# Module.net
KiCad netlist of a schematic drawn in EAGLE
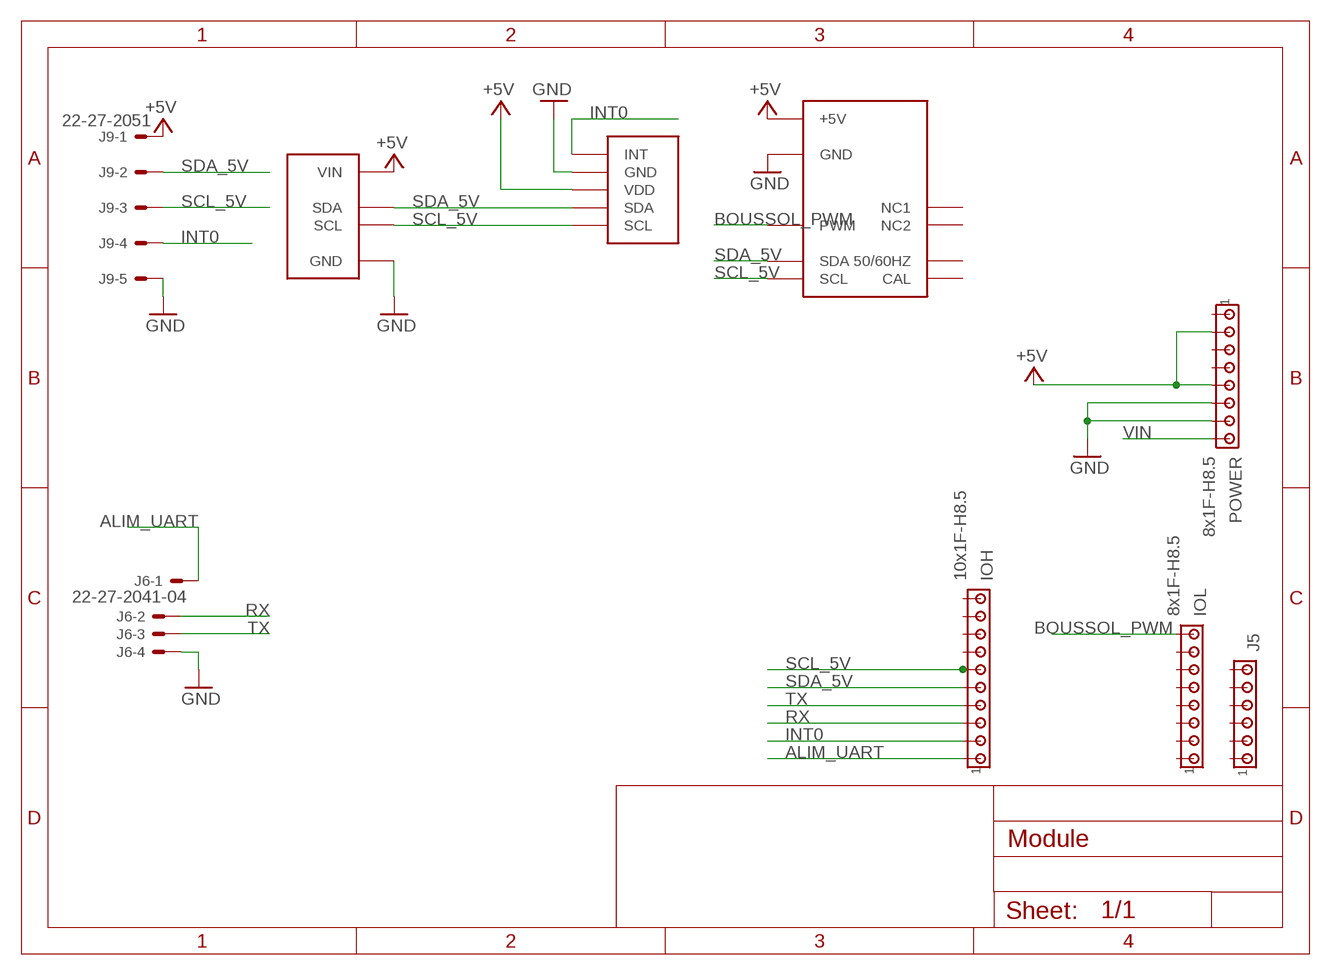
[diagram p0: schematic, sheet 1]

(export (version "E")
  (design (tool "Eeschema 10.0.6"))
  (components
    (comp (ref "IOH")
      (value "10x1F-H8.5")
      (footprint "eagle-import:10X10MTA")
      (libsource (lib "eagle-import") (part "MTA10-100"))
    )
    (comp (ref "IOL")
      (value "8x1F-H8.5")
      (footprint "eagle-import:10X08MTA")
      (libsource (lib "eagle-import") (part "MTA08-100"))
    )
    (comp (ref "J5")
      (value "MTA06-100")
      (footprint "eagle-import:10X06MTA")
      (libsource (lib "eagle-import") (part "MTA06-100"))
    )
    (comp (ref "J6")
      (value "22-27-2041-04")
      (footprint "eagle-import:6410-04")
      (libsource (lib "eagle-import") (part "22-?-0427-2041"))
    )
    (comp (ref "J9")
      (value "22-27-2051")
      (footprint "eagle-import:6410-05")
      (libsource (lib "eagle-import") (part "22-?-0527-2051"))
    )
    (comp (ref "POWER")
      (value "8x1F-H8.5")
      (footprint "eagle-import:10X08MTA")
      (libsource (lib "eagle-import") (part "MTA08-100"))
    )
    (comp (ref "U$1")
      (value "SRF10")
      (footprint "eagle-import:SRF10")
      (libsource (lib "eagle-import") (part "SRF10"))
    )
    (comp (ref "U$2")
      (value "MPU9150")
      (footprint "eagle-import:MPU9150")
      (libsource (lib "eagle-import") (part "MPU9150"))
    )
    (comp (ref "U$6")
      (value "CMPS03")
      (footprint "eagle-import:CMPS03")
      (libsource (lib "eagle-import") (part "CMPS03"))
    )
  )
  (nets
    (net (code "1") (name "+5V") (class "Default")
      (node (ref "J9") (pin "1") (pinfunction "S_1") (pintype "passive"))
      (node (ref "POWER") (pin "2") (pinfunction "2_2") (pintype "passive"))
      (node (ref "POWER") (pin "5") (pinfunction "5_5") (pintype "passive"))
      (node (ref "U$1") (pin "P$4") (pinfunction "VIN_P$4") (pintype "power_in"))
      (node (ref "U$2") (pin "P$3") (pinfunction "VDD_P$3") (pintype "power_in"))
      (node (ref "U$6") (pin "P$1") (pinfunction "+5V_P$1") (pintype "power_in"))
    )
    (net (code "2") (name "/ALIM_UART") (class "Default")
      (node (ref "IOH") (pin "1") (pinfunction "1_1") (pintype "passive"))
      (node (ref "J6") (pin "1") (pinfunction "S_1") (pintype "passive"))
    )
    (net (code "3") (name "/BOUSSOL_PWM") (class "Default")
      (node (ref "IOL") (pin "8") (pinfunction "8_8") (pintype "passive"))
      (node (ref "U$6") (pin "P$4") (pinfunction "PWM_P$4") (pintype "output"))
    )
    (net (code "4") (name "/INT0") (class "Default")
      (node (ref "IOH") (pin "2") (pinfunction "2_2") (pintype "passive"))
      (node (ref "J9") (pin "4") (pinfunction "S_4") (pintype "passive"))
      (node (ref "U$2") (pin "P$1") (pinfunction "INT_P$1") (pintype "output"))
    )
    (net (code "5") (name "/RX") (class "Default")
      (node (ref "IOH") (pin "3") (pinfunction "3_3") (pintype "passive"))
      (node (ref "J6") (pin "2") (pinfunction "S_2") (pintype "passive"))
    )
    (net (code "6") (name "/SCL_5V") (class "Default")
      (node (ref "IOH") (pin "6") (pinfunction "6_6") (pintype "passive"))
      (node (ref "J9") (pin "3") (pinfunction "S_3") (pintype "passive"))
      (node (ref "U$1") (pin "P$2") (pinfunction "SCL_P$2") (pintype "bidirectional"))
      (node (ref "U$2") (pin "P$5") (pinfunction "SCL_P$5") (pintype "bidirectional"))
      (node (ref "U$6") (pin "P$2") (pinfunction "SCL_P$2") (pintype "bidirectional"))
    )
    (net (code "7") (name "/SDA_5V") (class "Default")
      (node (ref "IOH") (pin "5") (pinfunction "5_5") (pintype "passive"))
      (node (ref "J9") (pin "2") (pinfunction "S_2") (pintype "passive"))
      (node (ref "U$1") (pin "P$3") (pinfunction "SDA_P$3") (pintype "bidirectional"))
      (node (ref "U$2") (pin "P$4") (pinfunction "SDA_P$4") (pintype "bidirectional"))
      (node (ref "U$6") (pin "P$3") (pinfunction "SDA_P$3") (pintype "bidirectional"))
    )
    (net (code "8") (name "/TX") (class "Default")
      (node (ref "IOH") (pin "4") (pinfunction "4_4") (pintype "passive"))
      (node (ref "J6") (pin "3") (pinfunction "S_3") (pintype "passive"))
    )
    (net (code "9") (name "/VIN") (class "Default")
      (node (ref "POWER") (pin "8") (pinfunction "8_8") (pintype "passive"))
    )
    (net (code "10") (name "GND") (class "Default")
      (node (ref "J6") (pin "4") (pinfunction "S_4") (pintype "passive"))
      (node (ref "J9") (pin "5") (pinfunction "S_5") (pintype "passive"))
      (node (ref "POWER") (pin "6") (pinfunction "6_6") (pintype "passive"))
      (node (ref "POWER") (pin "7") (pinfunction "7_7") (pintype "passive"))
      (node (ref "U$1") (pin "P$1") (pinfunction "GND_P$1") (pintype "power_in"))
      (node (ref "U$2") (pin "P$2") (pinfunction "GND_P$2") (pintype "power_in"))
      (node (ref "U$6") (pin "P$9") (pinfunction "GND_P$9") (pintype "power_in"))
    )
    (net (code "11") (name "unconnected-(IOH-Pad7)") (class "Default")
      (node (ref "IOH") (pin "7") (pinfunction "7_7") (pintype "passive"))
    )
    (net (code "12") (name "unconnected-(IOH-Pad8)") (class "Default")
      (node (ref "IOH") (pin "8") (pinfunction "8_8") (pintype "passive"))
    )
    (net (code "13") (name "unconnected-(IOH-Pad9)") (class "Default")
      (node (ref "IOH") (pin "9") (pinfunction "9_9") (pintype "passive"))
    )
    (net (code "14") (name "unconnected-(IOH-Pad10)") (class "Default")
      (node (ref "IOH") (pin "10") (pinfunction "10_10") (pintype "passive"))
    )
    (net (code "15") (name "unconnected-(IOL-Pad1)") (class "Default")
      (node (ref "IOL") (pin "1") (pinfunction "1_1") (pintype "passive"))
    )
    (net (code "16") (name "unconnected-(IOL-Pad2)") (class "Default")
      (node (ref "IOL") (pin "2") (pinfunction "2_2") (pintype "passive"))
    )
    (net (code "17") (name "unconnected-(IOL-Pad3)") (class "Default")
      (node (ref "IOL") (pin "3") (pinfunction "3_3") (pintype "passive"))
    )
    (net (code "18") (name "unconnected-(IOL-Pad4)") (class "Default")
      (node (ref "IOL") (pin "4") (pinfunction "4_4") (pintype "passive"))
    )
    (net (code "19") (name "unconnected-(IOL-Pad5)") (class "Default")
      (node (ref "IOL") (pin "5") (pinfunction "5_5") (pintype "passive"))
    )
    (net (code "20") (name "unconnected-(IOL-Pad6)") (class "Default")
      (node (ref "IOL") (pin "6") (pinfunction "6_6") (pintype "passive"))
    )
    (net (code "21") (name "unconnected-(IOL-Pad7)") (class "Default")
      (node (ref "IOL") (pin "7") (pinfunction "7_7") (pintype "passive"))
    )
    (net (code "22") (name "unconnected-(J5-1-Pad6)") (class "Default")
      (node (ref "J5") (pin "6") (pinfunction "1_6") (pintype "passive"))
    )
    (net (code "23") (name "unconnected-(J5-2-Pad5)") (class "Default")
      (node (ref "J5") (pin "5") (pinfunction "2_5") (pintype "passive"))
    )
    (net (code "24") (name "unconnected-(J5-3-Pad4)") (class "Default")
      (node (ref "J5") (pin "4") (pinfunction "3_4") (pintype "passive"))
    )
    (net (code "25") (name "unconnected-(J5-4-Pad3)") (class "Default")
      (node (ref "J5") (pin "3") (pinfunction "4_3") (pintype "passive"))
    )
    (net (code "26") (name "unconnected-(J5-5-Pad2)") (class "Default")
      (node (ref "J5") (pin "2") (pinfunction "5_2") (pintype "passive"))
    )
    (net (code "27") (name "unconnected-(J5-6-Pad1)") (class "Default")
      (node (ref "J5") (pin "1") (pinfunction "6_1") (pintype "passive"))
    )
    (net (code "28") (name "unconnected-(POWER-Pad1)") (class "Default")
      (node (ref "POWER") (pin "1") (pinfunction "1_1") (pintype "passive"))
    )
    (net (code "29") (name "unconnected-(POWER-Pad3)") (class "Default")
      (node (ref "POWER") (pin "3") (pinfunction "3_3") (pintype "passive"))
    )
    (net (code "30") (name "unconnected-(POWER-Pad4)") (class "Default")
      (node (ref "POWER") (pin "4") (pinfunction "4_4") (pintype "passive"))
    )
    (net (code "31") (name "unconnected-(U$6-50{slash}60HZ-PadP$7)") (class "Default")
      (node (ref "U$6") (pin "P$7") (pinfunction "50/60HZ_P$7") (pintype "bidirectional"))
    )
    (net (code "32") (name "unconnected-(U$6-CAL-PadP$6)") (class "Default")
      (node (ref "U$6") (pin "P$6") (pinfunction "CAL_P$6") (pintype "bidirectional"))
    )
    (net (code "33") (name "unconnected-(U$6-NC1-PadP$5)") (class "Default")
      (node (ref "U$6") (pin "P$5") (pinfunction "NC1_P$5") (pintype "no_connect"))
    )
    (net (code "34") (name "unconnected-(U$6-NC2-PadP$8)") (class "Default")
      (node (ref "U$6") (pin "P$8") (pinfunction "NC2_P$8") (pintype "no_connect"))
    )
  )
)
